# ESP-12E_B_Breakout_SMT.net
KiCad netlist of a schematic drawn in EAGLE
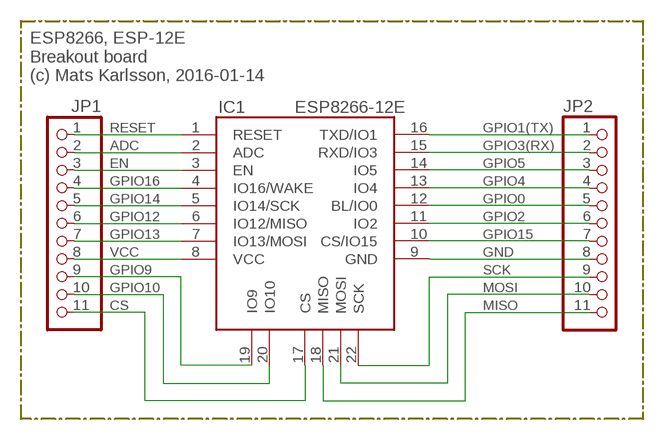
[diagram p0: schematic, sheet 1]

(export (version "E")
  (design (tool "Eeschema 10.0.6"))
  (components
    (comp (ref "IC1")
      (value "ESP8266-12E")
      (footprint "eagle-import:ESP8266-12E")
      (libsource (lib "eagle-import") (part "ESP8266-12E"))
    )
    (comp (ref "JP1")
      (value "PINHD-1X111X11_SMT")
      (footprint "eagle-import:1X11_SMT")
      (libsource (lib "eagle-import") (part "PINHD-1X111X11_SMT"))
    )
    (comp (ref "JP2")
      (value "PINHD-1X111X11_SMT")
      (footprint "eagle-import:1X11_SMT")
      (libsource (lib "eagle-import") (part "PINHD-1X111X11_SMT"))
    )
  )
  (nets
    (net (code "1") (name "/ADC") (class "Default")
      (node (ref "IC1") (pin "2") (pinfunction "ADC_2") (pintype "bidirectional"))
      (node (ref "JP1") (pin "2") (pinfunction "2_2") (pintype "passive"))
    )
    (net (code "2") (name "/CS") (class "Default")
      (node (ref "IC1") (pin "17") (pinfunction "CS_17") (pintype "bidirectional"))
      (node (ref "JP1") (pin "11") (pinfunction "11_11") (pintype "passive"))
    )
    (net (code "3") (name "/EN") (class "Default")
      (node (ref "IC1") (pin "3") (pinfunction "EN_3") (pintype "bidirectional"))
      (node (ref "JP1") (pin "3") (pinfunction "3_3") (pintype "passive"))
    )
    (net (code "4") (name "/GND") (class "Default")
      (node (ref "IC1") (pin "9") (pinfunction "GND_9") (pintype "power_in"))
      (node (ref "JP2") (pin "8") (pinfunction "8_8") (pintype "passive"))
    )
    (net (code "5") (name "/GPIO0") (class "Default")
      (node (ref "IC1") (pin "12") (pinfunction "BL/IO0_12") (pintype "bidirectional"))
      (node (ref "JP2") (pin "5") (pinfunction "5_5") (pintype "passive"))
    )
    (net (code "6") (name "/GPIO1(TX)") (class "Default")
      (node (ref "IC1") (pin "16") (pinfunction "TXD/IO1_16") (pintype "bidirectional"))
      (node (ref "JP2") (pin "1") (pinfunction "1_1") (pintype "passive"))
    )
    (net (code "7") (name "/GPIO2") (class "Default")
      (node (ref "IC1") (pin "11") (pinfunction "IO2_11") (pintype "bidirectional"))
      (node (ref "JP2") (pin "6") (pinfunction "6_6") (pintype "passive"))
    )
    (net (code "8") (name "/GPIO3(RX)") (class "Default")
      (node (ref "IC1") (pin "15") (pinfunction "RXD/IO3_15") (pintype "bidirectional"))
      (node (ref "JP2") (pin "2") (pinfunction "2_2") (pintype "passive"))
    )
    (net (code "9") (name "/GPIO4") (class "Default")
      (node (ref "IC1") (pin "13") (pinfunction "IO4_13") (pintype "bidirectional"))
      (node (ref "JP2") (pin "4") (pinfunction "4_4") (pintype "passive"))
    )
    (net (code "10") (name "/GPIO5") (class "Default")
      (node (ref "IC1") (pin "14") (pinfunction "IO5_14") (pintype "bidirectional"))
      (node (ref "JP2") (pin "3") (pinfunction "3_3") (pintype "passive"))
    )
    (net (code "11") (name "/GPIO9") (class "Default")
      (node (ref "IC1") (pin "19") (pinfunction "IO9_19") (pintype "bidirectional"))
      (node (ref "JP1") (pin "9") (pinfunction "9_9") (pintype "passive"))
    )
    (net (code "12") (name "/GPIO10") (class "Default")
      (node (ref "IC1") (pin "20") (pinfunction "IO10_20") (pintype "bidirectional"))
      (node (ref "JP1") (pin "10") (pinfunction "10_10") (pintype "passive"))
    )
    (net (code "13") (name "/GPIO12") (class "Default")
      (node (ref "IC1") (pin "6") (pinfunction "IO12/MISO_6") (pintype "bidirectional"))
      (node (ref "JP1") (pin "6") (pinfunction "6_6") (pintype "passive"))
    )
    (net (code "14") (name "/GPIO13") (class "Default")
      (node (ref "IC1") (pin "7") (pinfunction "IO13/MOSI_7") (pintype "bidirectional"))
      (node (ref "JP1") (pin "7") (pinfunction "7_7") (pintype "passive"))
    )
    (net (code "15") (name "/GPIO14") (class "Default")
      (node (ref "IC1") (pin "5") (pinfunction "IO14/SCK_5") (pintype "bidirectional"))
      (node (ref "JP1") (pin "5") (pinfunction "5_5") (pintype "passive"))
    )
    (net (code "16") (name "/GPIO15") (class "Default")
      (node (ref "IC1") (pin "10") (pinfunction "CS/IO15_10") (pintype "bidirectional"))
      (node (ref "JP2") (pin "7") (pinfunction "7_7") (pintype "passive"))
    )
    (net (code "17") (name "/GPIO16") (class "Default")
      (node (ref "IC1") (pin "4") (pinfunction "IO16/WAKE_4") (pintype "bidirectional"))
      (node (ref "JP1") (pin "4") (pinfunction "4_4") (pintype "passive"))
    )
    (net (code "18") (name "/MISO") (class "Default")
      (node (ref "IC1") (pin "18") (pinfunction "MISO_18") (pintype "bidirectional"))
      (node (ref "JP2") (pin "11") (pinfunction "11_11") (pintype "passive"))
    )
    (net (code "19") (name "/MOSI") (class "Default")
      (node (ref "IC1") (pin "21") (pinfunction "MOSI_21") (pintype "bidirectional"))
      (node (ref "JP2") (pin "10") (pinfunction "10_10") (pintype "passive"))
    )
    (net (code "20") (name "/RESET") (class "Default")
      (node (ref "IC1") (pin "1") (pinfunction "RESET_1") (pintype "bidirectional"))
      (node (ref "JP1") (pin "1") (pinfunction "1_1") (pintype "passive"))
    )
    (net (code "21") (name "/SCK") (class "Default")
      (node (ref "IC1") (pin "22") (pinfunction "SCK_22") (pintype "bidirectional"))
      (node (ref "JP2") (pin "9") (pinfunction "9_9") (pintype "passive"))
    )
    (net (code "22") (name "/VCC") (class "Default")
      (node (ref "IC1") (pin "8") (pinfunction "VCC_8") (pintype "power_in"))
      (node (ref "JP1") (pin "8") (pinfunction "8_8") (pintype "passive"))
    )
  )
)
